# 111.net
KiCad netlist of a schematic drawn in Altium Designer
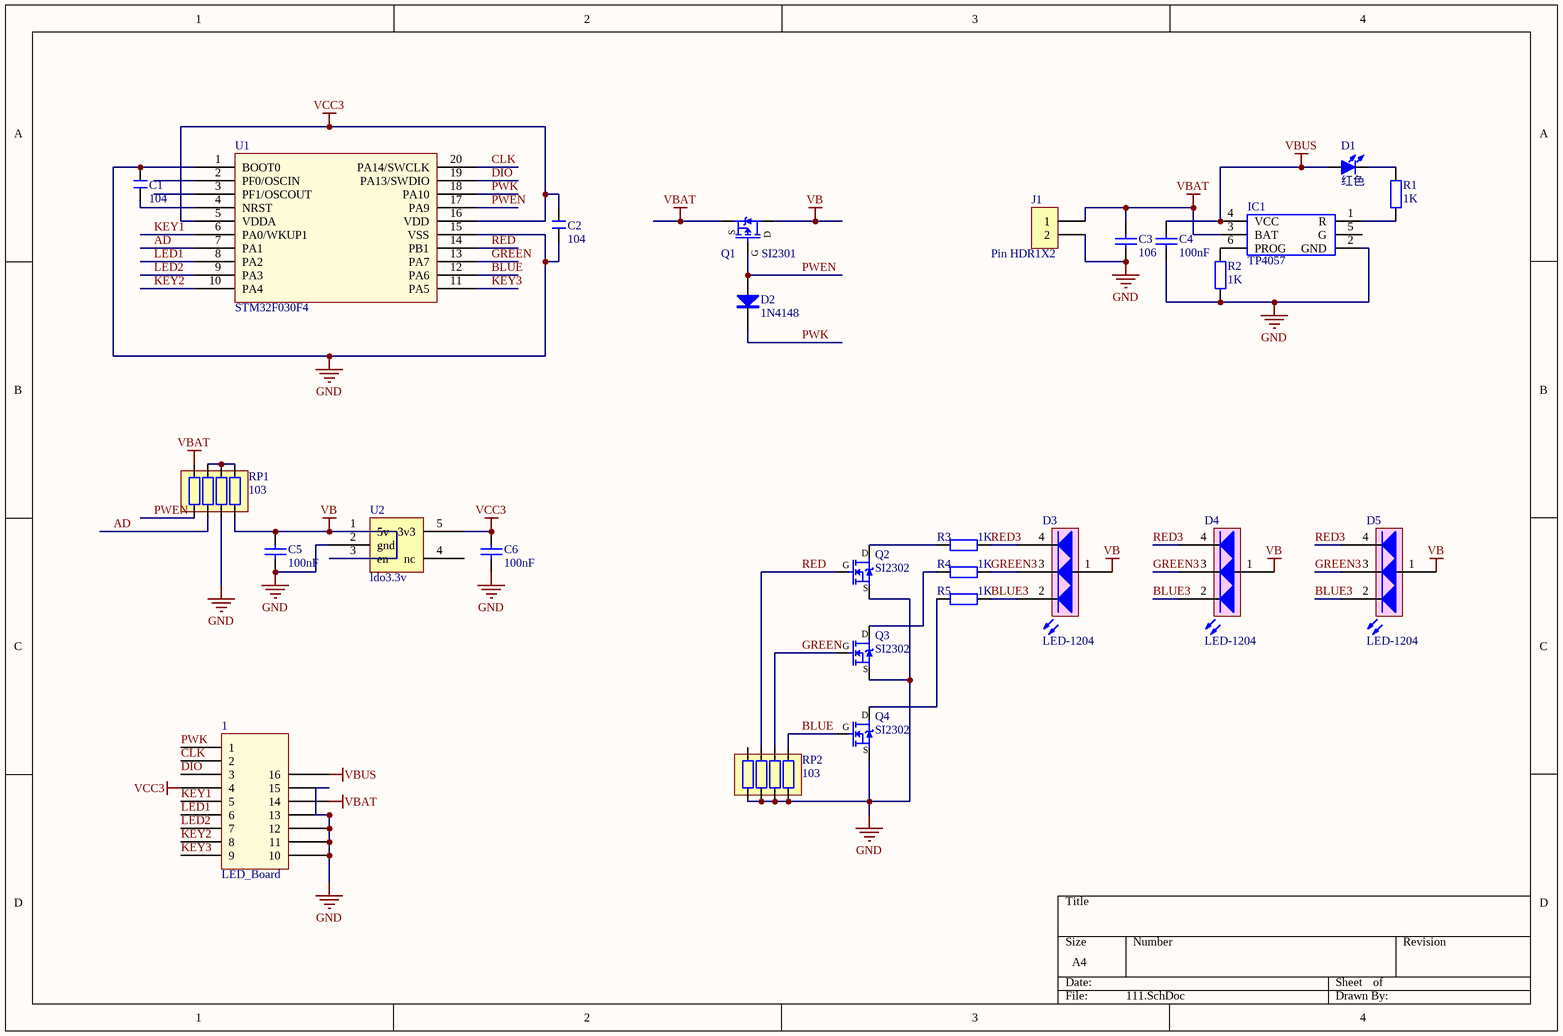
[diagram p0: 111.SchDoc]

(export (version "E")
  (design (tool "Eeschema 10.0.6"))
  (components
    (comp (ref "1") (value "LED_Board") (footprint "LED_KO") (libsource (lib "fszhang") (part "LED_Board")))
    (comp (ref "C1")
      (value "104")
      (footprint "C 0402_M")
      (description "无极性贴片电容")
      (libsource (lib "3.1   - 电阻-电容-电感") (part "C"))
    )
    (comp (ref "C2")
      (value "104")
      (footprint "C 0402_M")
      (description "无极性贴片电容")
      (libsource (lib "3.1   - 电阻-电容-电感") (part "C"))
    )
    (comp (ref "C3")
      (value "106")
      (footprint "C-RAD-0805")
      (description "无极性电容")
      (fields (field (name "Comment") "Cap") (field (name "PUBLISHER") "Altium Limited"))
      (libsource (lib "fszhang") (part "Cap"))
    )
    (comp (ref "C4")
      (value "100nF")
      (footprint "C-RAD-0603")
      (description "无极性电容")
      (fields (field (name "Comment") "Cap") (field (name "PUBLISHER") "Altium Limited"))
      (libsource (lib "fszhang") (part "Cap"))
    )
    (comp (ref "C5")
      (value "100nF")
      (footprint "C-RAD-0603")
      (description "无极性电容")
      (fields (field (name "Comment") "Cap") (field (name "PUBLISHER") "Altium Limited"))
      (libsource (lib "fszhang") (part "Cap"))
    )
    (comp (ref "C6")
      (value "100nF")
      (footprint "C-RAD-0603")
      (description "无极性电容")
      (fields (field (name "Comment") "Cap") (field (name "PUBLISHER") "Altium Limited"))
      (libsource (lib "fszhang") (part "Cap"))
    )
    (comp (ref "D1")
      (value "红色")
      (footprint "LED 0603R")
      (description "贴片LED")
      (libsource (lib "9.1   - LED") (part "LED-SMD"))
    )
    (comp (ref "D2")
      (value "1N4148")
      (footprint "SOD-323")
      (description "高速开关二极管")
      (libsource (lib "8.1   - 二极管-整流桥") (part "1N4148"))
    )
    (comp (ref "D3")
      (value "LED-1204")
      (footprint "LED_1204")
      (description "三基色LED")
      (fields (field (name "PUBLISHER") "Altium Limited"))
      (libsource (lib "fszhang") (part "LED-1204"))
    )
    (comp (ref "D4")
      (value "LED-1204")
      (footprint "LED_1204")
      (description "三基色LED")
      (fields (field (name "PUBLISHER") "Altium Limited"))
      (libsource (lib "fszhang") (part "LED-1204"))
    )
    (comp (ref "D5")
      (value "LED-1204")
      (footprint "LED_1204")
      (description "三基色LED")
      (fields (field (name "PUBLISHER") "Altium Limited"))
      (libsource (lib "fszhang") (part "LED-1204"))
    )
    (comp (ref "IC1") (value "TP4057") (footprint "SOT23-6M") (libsource (lib "常用") (part "TP4057")))
    (comp (ref "J1")
      (value "Pin HDR1X2")
      (footprint "Pin HDR1X2/2.54mm-S")
      (libsource (lib "排针") (part "Pin HDR1X2"))
    )
    (comp (ref "Q1")
      (value "SI2301")
      (footprint "SOT23-3N")
      (description "P沟道 20V/2.8A")
      (libsource (lib "6.1   - 场效应管-可控硅") (part "SI2301"))
    )
    (comp (ref "Q2")
      (value "SI2302")
      (footprint "SOT23-3N")
      (description "N沟道 20V/3A")
      (libsource (lib "6.1   - 场效应管-可控硅") (part "SI2302"))
    )
    (comp (ref "Q3")
      (value "SI2302")
      (footprint "SOT23-3N")
      (description "N沟道 20V/3A")
      (libsource (lib "6.1   - 场效应管-可控硅") (part "SI2302"))
    )
    (comp (ref "Q4")
      (value "SI2302")
      (footprint "SOT23-3N")
      (description "N沟道 20V/3A")
      (libsource (lib "6.1   - 场效应管-可控硅") (part "SI2302"))
    )
    (comp (ref "R1")
      (value "1K")
      (footprint "R 0402_M")
      (description "贴片电阻")
      (libsource (lib "3.1   - 电阻-电容-电感") (part "R"))
    )
    (comp (ref "R2")
      (value "1K")
      (footprint "R 0402_M")
      (description "贴片电阻")
      (libsource (lib "3.1   - 电阻-电容-电感") (part "R"))
    )
    (comp (ref "R3")
      (value "1K")
      (footprint "0603-1")
      (description "贴片电阻")
      (fields (field (name "Comment") "Res1") (field (name "PUBLISHER") "Altium Limited"))
      (libsource (lib "fszhang") (part "Res1"))
    )
    (comp (ref "R4")
      (value "1K")
      (footprint "0603-1")
      (description "贴片电阻")
      (fields (field (name "Comment") "Res1") (field (name "PUBLISHER") "Altium Limited"))
      (libsource (lib "fszhang") (part "Res1"))
    )
    (comp (ref "R5")
      (value "1K")
      (footprint "0603-1")
      (description "贴片电阻")
      (fields (field (name "Comment") "Res1") (field (name "PUBLISHER") "Altium Limited"))
      (libsource (lib "fszhang") (part "Res1"))
    )
    (comp (ref "RP1")
      (value "103")
      (footprint "RCA-8P4R-0402")
      (description "贴片网络排阻")
      (libsource (lib "3.1   - 电阻-电容-电感") (part "R-8P4R"))
    )
    (comp (ref "RP2")
      (value "103")
      (footprint "RCA-8P4R-0402")
      (description "贴片网络排阻")
      (libsource (lib "3.1   - 电阻-电容-电感") (part "R-8P4R"))
    )
    (comp (ref "U1")
      (value "STM32F030F4")
      (footprint "TSSOP20")
      (libsource (lib "fszhang") (part "STM32F030F4"))
    )
    (comp (ref "U2") (value "ldo3.3v") (footprint "SOT23-5") (libsource (lib "3.3ldo") (part "Component_1")))
  )
  (nets
    (net (code "1") (name "/AD") (class "Default")
      (node (ref "RP1") (pin "2") (pinfunction "2_2") (pintype "passive"))
      (node (ref "U1") (pin "7") (pinfunction "PA1_7") (pintype "passive"))
    )
    (net (code "2") (name "/BLUE") (class "Default")
      (node (ref "Q4") (pin "1") (pinfunction "G_1") (pintype "passive"))
      (node (ref "RP2") (pin "5") (pinfunction "5_5") (pintype "passive"))
      (node (ref "U1") (pin "12") (pinfunction "PA6_12") (pintype "passive"))
    )
    (net (code "3") (name "/BLUE3") (class "Default")
      (node (ref "D3") (pin "2") (pinfunction "B_2") (pintype "passive"))
      (node (ref "D4") (pin "2") (pinfunction "B_2") (pintype "passive"))
      (node (ref "D5") (pin "2") (pinfunction "B_2") (pintype "passive"))
      (node (ref "R5") (pin "2") (pinfunction "2_2") (pintype "passive"))
    )
    (net (code "4") (name "/CLK") (class "Default")
      (node (ref "1") (pin "2") (pinfunction "2_2") (pintype "passive"))
      (node (ref "U1") (pin "20") (pinfunction "PA14/SWCLK_20") (pintype "passive"))
    )
    (net (code "5") (name "/DIO") (class "Default")
      (node (ref "1") (pin "3") (pinfunction "3_3") (pintype "passive"))
      (node (ref "U1") (pin "19") (pinfunction "PA13/SWDIO_19") (pintype "passive"))
    )
    (net (code "6") (name "/GREEN") (class "Default")
      (node (ref "Q3") (pin "1") (pinfunction "G_1") (pintype "passive"))
      (node (ref "RP2") (pin "6") (pinfunction "6_6") (pintype "passive"))
      (node (ref "U1") (pin "13") (pinfunction "PA7_13") (pintype "passive"))
    )
    (net (code "7") (name "/GREEN3") (class "Default")
      (node (ref "D3") (pin "3") (pinfunction "G_3") (pintype "passive"))
      (node (ref "D4") (pin "3") (pinfunction "G_3") (pintype "passive"))
      (node (ref "D5") (pin "3") (pinfunction "G_3") (pintype "passive"))
      (node (ref "R4") (pin "2") (pinfunction "2_2") (pintype "passive"))
    )
    (net (code "8") (name "/KEY1") (class "Default")
      (node (ref "1") (pin "5") (pinfunction "5_5") (pintype "passive"))
      (node (ref "U1") (pin "6") (pinfunction "PA0/WKUP1_6") (pintype "passive"))
    )
    (net (code "9") (name "/KEY2") (class "Default")
      (node (ref "1") (pin "8") (pinfunction "8_8") (pintype "passive"))
      (node (ref "U1") (pin "10") (pinfunction "PA4_10") (pintype "passive"))
    )
    (net (code "10") (name "/KEY3") (class "Default")
      (node (ref "1") (pin "9") (pinfunction "9_9") (pintype "passive"))
      (node (ref "U1") (pin "11") (pinfunction "PA5_11") (pintype "passive"))
    )
    (net (code "11") (name "/LED1") (class "Default")
      (node (ref "1") (pin "6") (pinfunction "6_6") (pintype "passive"))
      (node (ref "U1") (pin "8") (pinfunction "PA2_8") (pintype "passive"))
    )
    (net (code "12") (name "/LED2") (class "Default")
      (node (ref "1") (pin "7") (pinfunction "7_7") (pintype "passive"))
      (node (ref "U1") (pin "9") (pinfunction "PA3_9") (pintype "passive"))
    )
    (net (code "13") (name "/PWEN") (class "Default")
      (node (ref "D2") (pin "A") (pinfunction "A_A") (pintype "passive"))
      (node (ref "Q1") (pin "1") (pinfunction "G_1") (pintype "passive"))
      (node (ref "RP1") (pin "1") (pinfunction "1_1") (pintype "passive"))
      (node (ref "U1") (pin "17") (pinfunction "PA9_17") (pintype "passive"))
    )
    (net (code "14") (name "/PWK") (class "Default")
      (node (ref "1") (pin "1") (pinfunction "1_1") (pintype "passive"))
      (node (ref "D2") (pin "K") (pinfunction "K_K") (pintype "passive"))
      (node (ref "U1") (pin "18") (pinfunction "PA10_18") (pintype "passive"))
    )
    (net (code "15") (name "/RED") (class "Default")
      (node (ref "Q2") (pin "1") (pinfunction "G_1") (pintype "passive"))
      (node (ref "RP2") (pin "7") (pinfunction "7_7") (pintype "passive"))
      (node (ref "U1") (pin "14") (pinfunction "PB1_14") (pintype "passive"))
    )
    (net (code "16") (name "/RED3") (class "Default")
      (node (ref "D3") (pin "4") (pinfunction "R_4") (pintype "passive"))
      (node (ref "D4") (pin "4") (pinfunction "R_4") (pintype "passive"))
      (node (ref "D5") (pin "4") (pinfunction "R_4") (pintype "passive"))
      (node (ref "R3") (pin "2") (pinfunction "2_2") (pintype "passive"))
    )
    (net (code "17") (name "GND") (class "Default")
      (node (ref "1") (pin "10") (pinfunction "10_10") (pintype "passive"))
      (node (ref "1") (pin "11") (pinfunction "11_11") (pintype "passive"))
      (node (ref "1") (pin "12") (pinfunction "12_12") (pintype "passive"))
      (node (ref "1") (pin "13") (pinfunction "13_13") (pintype "passive"))
      (node (ref "1") (pin "15") (pinfunction "15_15") (pintype "passive"))
      (node (ref "C1") (pin "2") (pinfunction "2_2") (pintype "passive"))
      (node (ref "C2") (pin "1") (pinfunction "1_1") (pintype "passive"))
      (node (ref "C3") (pin "1") (pinfunction "1_1") (pintype "passive"))
      (node (ref "C4") (pin "1") (pinfunction "1_1") (pintype "passive"))
      (node (ref "C5") (pin "1") (pinfunction "1_1") (pintype "passive"))
      (node (ref "C6") (pin "1") (pinfunction "1_1") (pintype "passive"))
      (node (ref "IC1") (pin "2") (pinfunction "GND_2") (pintype "passive"))
      (node (ref "J1") (pin "2") (pinfunction "2_2") (pintype "passive"))
      (node (ref "Q2") (pin "2") (pinfunction "S_2") (pintype "passive"))
      (node (ref "Q3") (pin "2") (pinfunction "S_2") (pintype "passive"))
      (node (ref "Q4") (pin "2") (pinfunction "S_2") (pintype "passive"))
      (node (ref "R2") (pin "1") (pinfunction "1_1") (pintype "passive"))
      (node (ref "RP1") (pin "3") (pinfunction "3_3") (pintype "passive"))
      (node (ref "RP2") (pin "1") (pinfunction "1_1") (pintype "passive"))
      (node (ref "RP2") (pin "2") (pinfunction "2_2") (pintype "passive"))
      (node (ref "RP2") (pin "3") (pinfunction "3_3") (pintype "passive"))
      (node (ref "RP2") (pin "4") (pinfunction "4_4") (pintype "passive"))
      (node (ref "U1") (pin "1") (pinfunction "BOOT0_1") (pintype "passive"))
      (node (ref "U1") (pin "15") (pinfunction "VSS_15") (pintype "passive"))
      (node (ref "U2") (pin "2") (pinfunction "gnd_2") (pintype "passive"))
    )
    (net (code "18") (name "Net-(D1-K)") (class "Default")
      (node (ref "D1") (pin "2") (pinfunction "K_2") (pintype "passive"))
      (node (ref "R1") (pin "2") (pinfunction "2_2") (pintype "passive"))
    )
    (net (code "19") (name "Net-(IC1-PROG)") (class "Default")
      (node (ref "IC1") (pin "6") (pinfunction "PROG_6") (pintype "passive"))
      (node (ref "R2") (pin "2") (pinfunction "2_2") (pintype "passive"))
    )
    (net (code "20") (name "Net-(IC1-R)") (class "Default")
      (node (ref "IC1") (pin "1") (pinfunction "R_1") (pintype "passive"))
      (node (ref "R1") (pin "1") (pinfunction "1_1") (pintype "passive"))
    )
    (net (code "21") (name "Net-(Q2-D)") (class "Default")
      (node (ref "Q2") (pin "3") (pinfunction "D_3") (pintype "passive"))
      (node (ref "R3") (pin "1") (pinfunction "1_1") (pintype "passive"))
    )
    (net (code "22") (name "Net-(Q3-D)") (class "Default")
      (node (ref "Q3") (pin "3") (pinfunction "D_3") (pintype "passive"))
      (node (ref "R4") (pin "1") (pinfunction "1_1") (pintype "passive"))
    )
    (net (code "23") (name "Net-(Q4-D)") (class "Default")
      (node (ref "Q4") (pin "3") (pinfunction "D_3") (pintype "passive"))
      (node (ref "R5") (pin "1") (pinfunction "1_1") (pintype "passive"))
    )
    (net (code "24") (name "Net-(RP1-Pad5)") (class "Default")
      (node (ref "RP1") (pin "5") (pinfunction "5_5") (pintype "passive"))
      (node (ref "RP1") (pin "6") (pinfunction "6_6") (pintype "passive"))
      (node (ref "RP1") (pin "7") (pinfunction "7_7") (pintype "passive"))
    )
    (net (code "25") (name "Net-(U1-NRST)") (class "Default")
      (node (ref "C1") (pin "1") (pinfunction "1_1") (pintype "passive"))
      (node (ref "U1") (pin "4") (pinfunction "NRST_4") (pintype "passive"))
    )
    (net (code "26") (name "VB") (class "Default")
      (node (ref "C5") (pin "2") (pinfunction "2_2") (pintype "passive"))
      (node (ref "D3") (pin "1") (pinfunction "1_1") (pintype "passive"))
      (node (ref "D4") (pin "1") (pinfunction "1_1") (pintype "passive"))
      (node (ref "D5") (pin "1") (pinfunction "1_1") (pintype "passive"))
      (node (ref "Q1") (pin "3") (pinfunction "D_3") (pintype "passive"))
      (node (ref "RP1") (pin "4") (pinfunction "4_4") (pintype "passive"))
      (node (ref "U2") (pin "1") (pinfunction "5v_1") (pintype "passive"))
      (node (ref "U2") (pin "3") (pinfunction "en_3") (pintype "passive"))
    )
    (net (code "27") (name "VBAT") (class "Default")
      (node (ref "1") (pin "14") (pinfunction "14_14") (pintype "passive"))
      (node (ref "C3") (pin "2") (pinfunction "2_2") (pintype "passive"))
      (node (ref "IC1") (pin "3") (pinfunction "BAT_3") (pintype "passive"))
      (node (ref "J1") (pin "1") (pinfunction "1_1") (pintype "passive"))
      (node (ref "Q1") (pin "2") (pinfunction "S_2") (pintype "passive"))
      (node (ref "RP1") (pin "8") (pinfunction "8_8") (pintype "passive"))
    )
    (net (code "28") (name "VBUS") (class "Default")
      (node (ref "1") (pin "16") (pinfunction "16_16") (pintype "passive"))
      (node (ref "C4") (pin "2") (pinfunction "2_2") (pintype "passive"))
      (node (ref "D1") (pin "1") (pinfunction "A_1") (pintype "passive"))
      (node (ref "IC1") (pin "4") (pinfunction "VCC_4") (pintype "passive"))
    )
    (net (code "29") (name "VCC3") (class "Default")
      (node (ref "1") (pin "4") (pinfunction "4_4") (pintype "passive"))
      (node (ref "C2") (pin "2") (pinfunction "2_2") (pintype "passive"))
      (node (ref "C6") (pin "2") (pinfunction "2_2") (pintype "passive"))
      (node (ref "U1") (pin "16") (pinfunction "VDD_16") (pintype "passive"))
      (node (ref "U1") (pin "5") (pinfunction "VDDA_5") (pintype "passive"))
      (node (ref "U2") (pin "5") (pinfunction "3v3_5") (pintype "passive"))
    )
    (net (code "30") (name "unconnected-(IC1-G-Pad5)") (class "Default")
      (node (ref "IC1") (pin "5") (pinfunction "G_5") (pintype "passive"))
    )
    (net (code "31") (name "unconnected-(RP2-Pad8)") (class "Default")
      (node (ref "RP2") (pin "8") (pinfunction "8_8") (pintype "passive"))
    )
    (net (code "32") (name "unconnected-(U1-PF0{slash}OSCIN-Pad2)") (class "Default")
      (node (ref "U1") (pin "2") (pinfunction "PF0/OSCIN_2") (pintype "passive"))
    )
    (net (code "33") (name "unconnected-(U1-PF1{slash}OSCOUT-Pad3)") (class "Default")
      (node (ref "U1") (pin "3") (pinfunction "PF1/OSCOUT_3") (pintype "passive"))
    )
    (net (code "34") (name "unconnected-(U2-nc-Pad4)") (class "Default")
      (node (ref "U2") (pin "4") (pinfunction "nc_4") (pintype "passive"))
    )
  )
)
